# NIRGM_V9.net
KiCad netlist of a schematic drawn in EAGLE
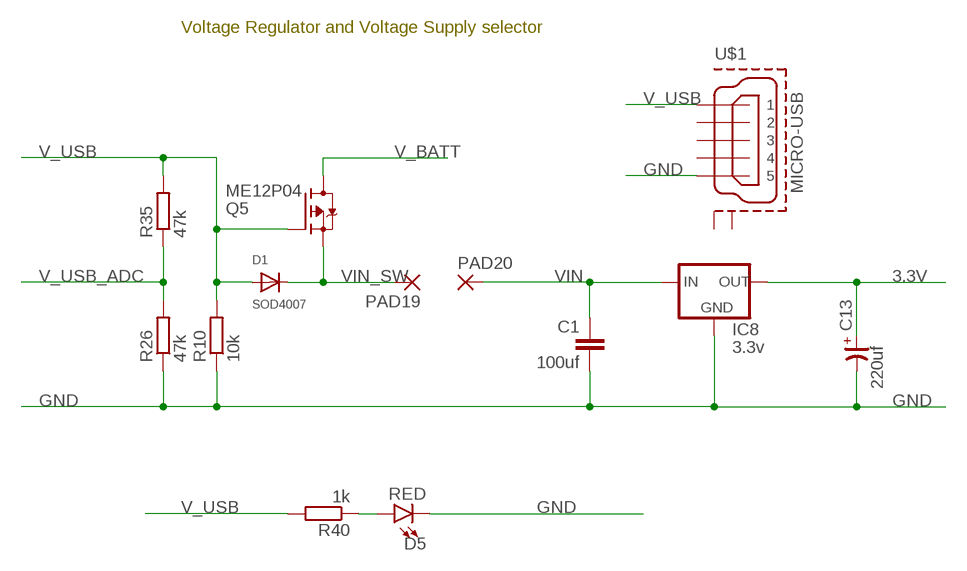
[diagram p0: schematic, sheet 1]
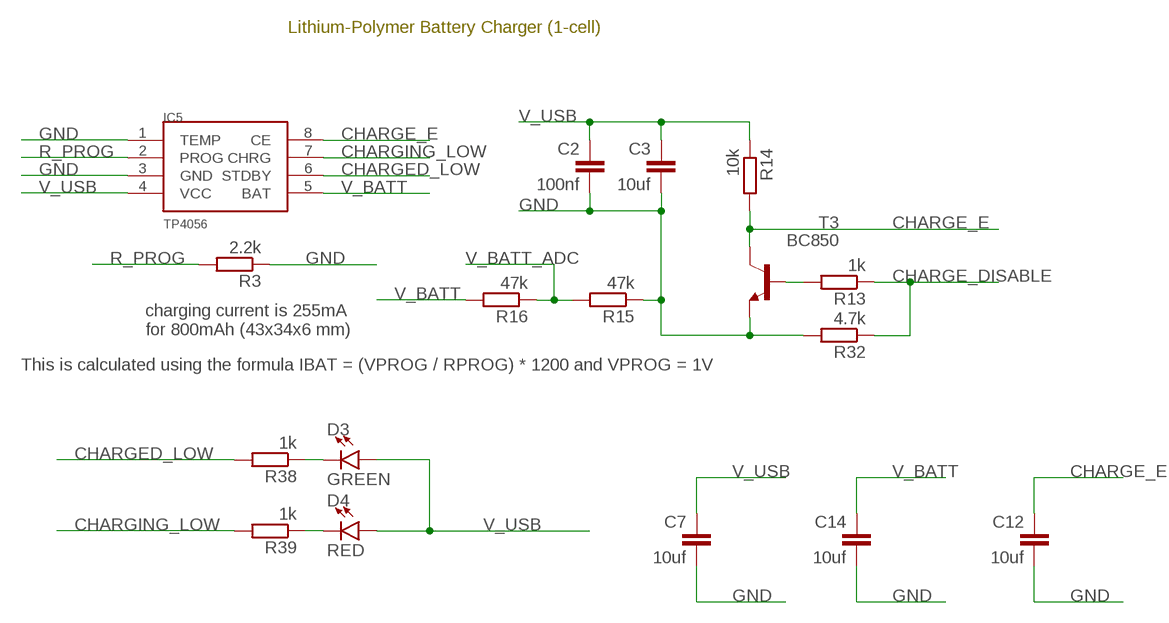
[diagram p1: schematic, sheet 2]
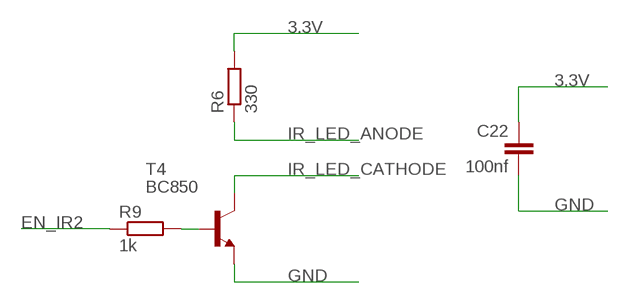
[diagram p2: schematic, sheet 3]
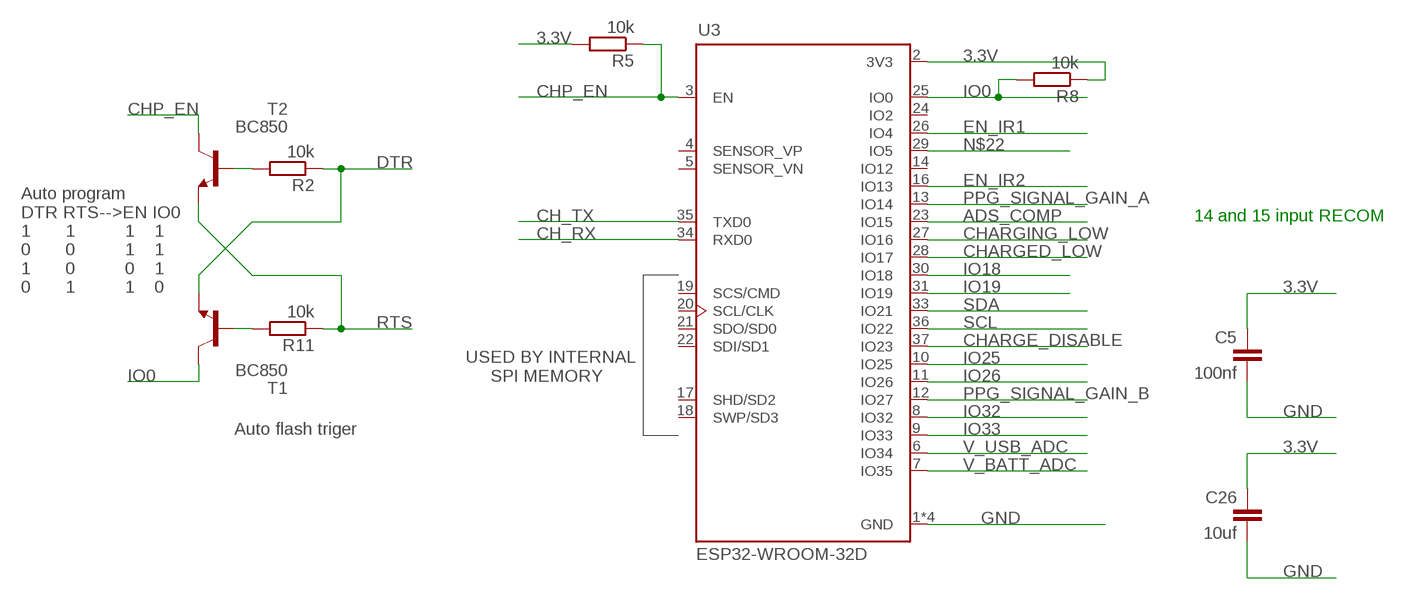
[diagram p3: schematic, sheet 4]
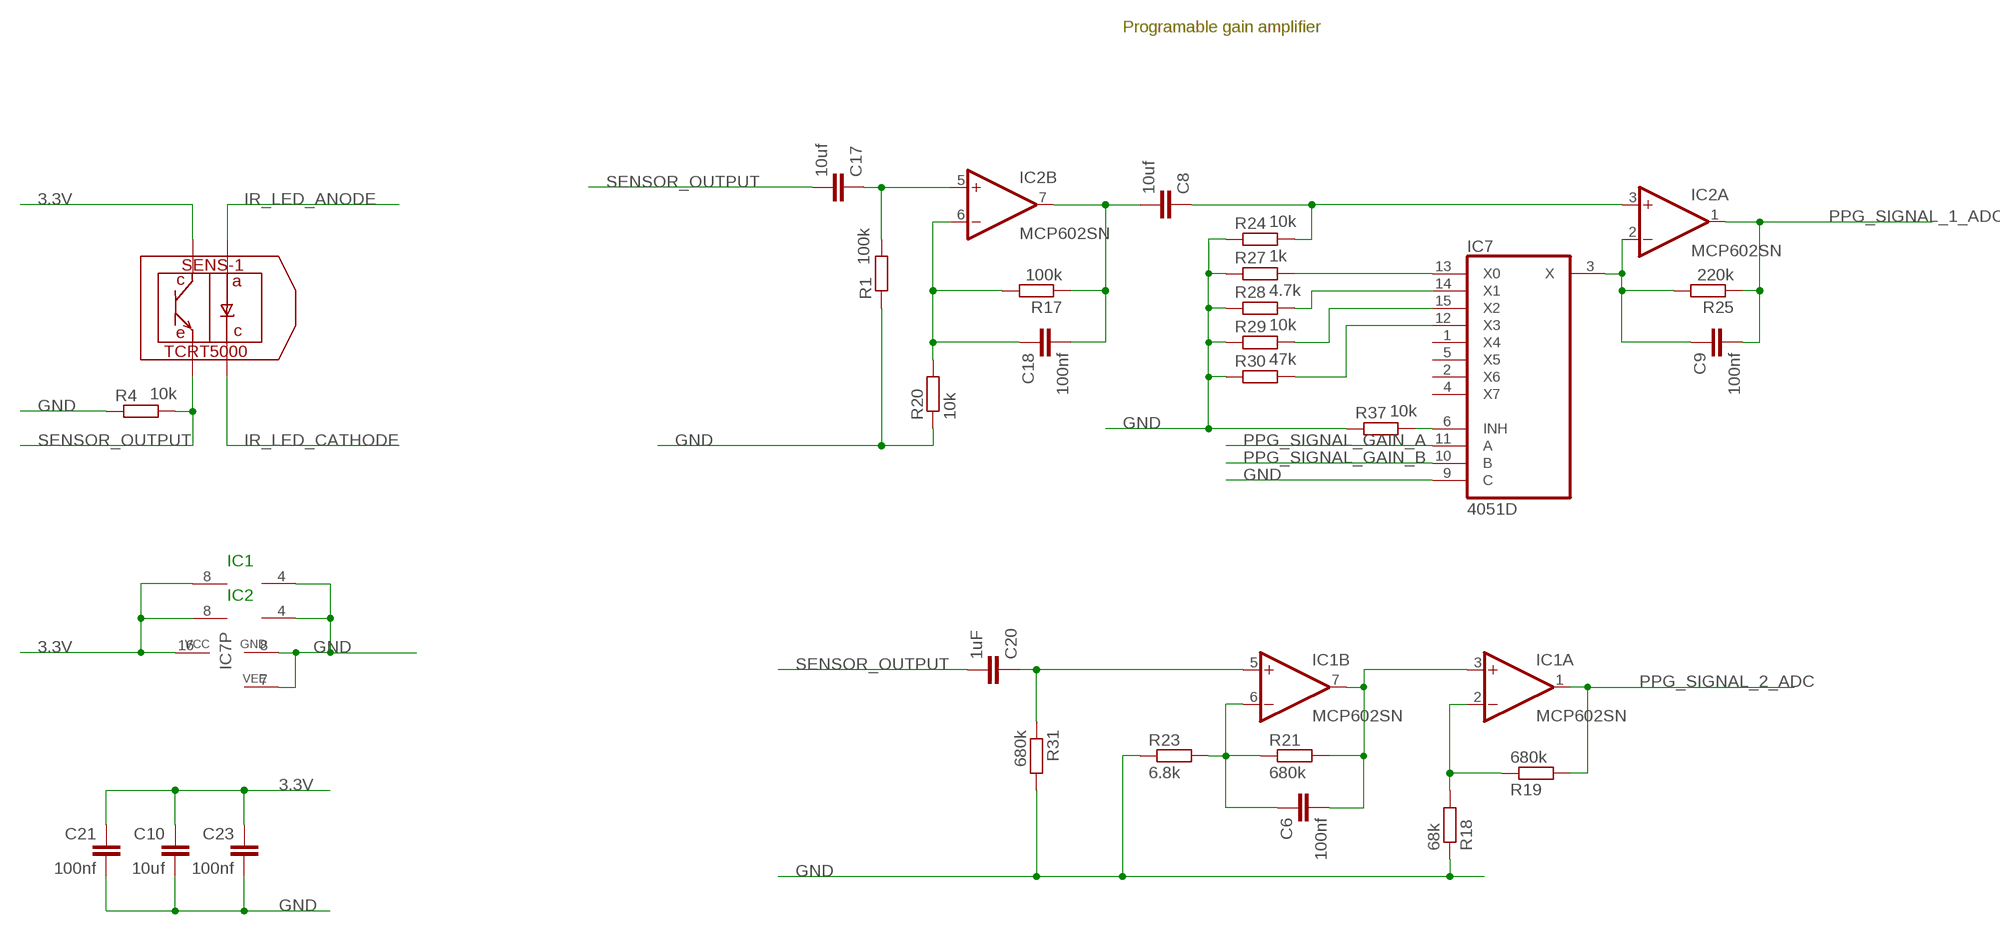
[diagram p4: schematic, sheet 5]
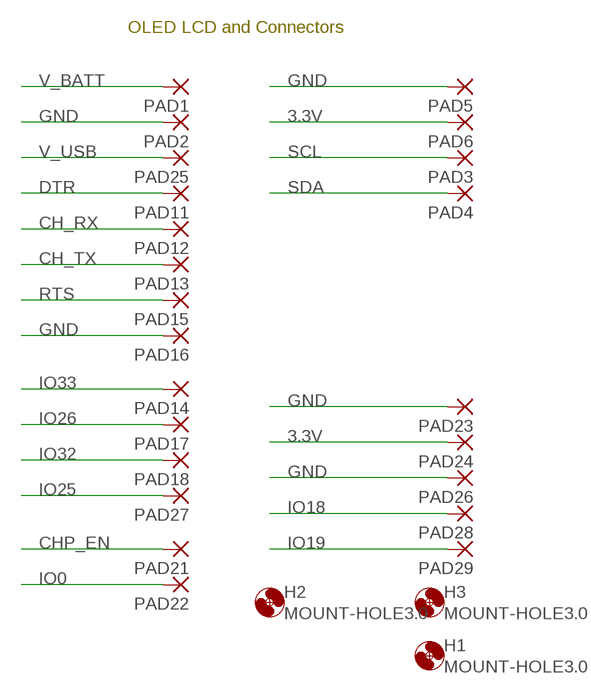
[diagram p5: schematic, sheet 6]
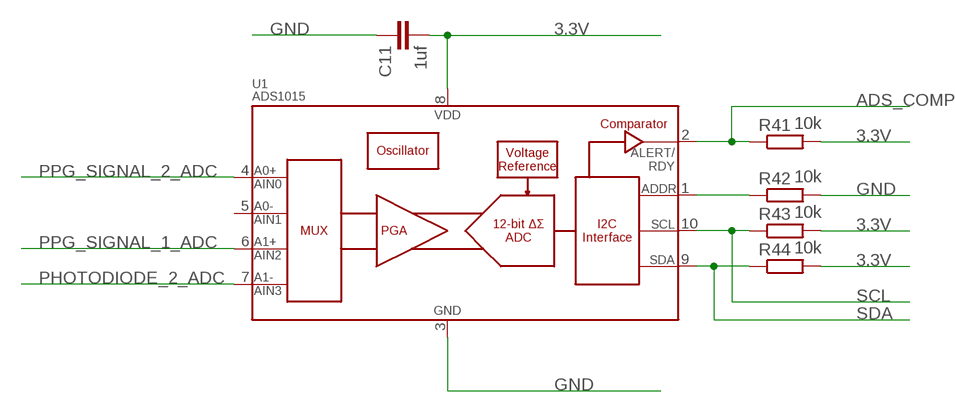
[diagram p6: schematic, sheet 7]

(export (version "E")
  (design (tool "Eeschema 10.0.6"))
  (components
    (comp (ref "H1")
      (value "MOUNT-HOLE3.0")
      (footprint "eagle-import:3,0")
      (libsource (lib "eagle-import") (part "MOUNT-HOLE3.0"))
    )
    (comp (ref "H2")
      (value "MOUNT-HOLE3.0")
      (footprint "eagle-import:3,0")
      (libsource (lib "eagle-import") (part "MOUNT-HOLE3.0"))
    )
    (comp (ref "H3")
      (value "MOUNT-HOLE3.0")
      (footprint "eagle-import:3,0")
      (libsource (lib "eagle-import") (part "MOUNT-HOLE3.0"))
    )
    (comp (ref "PAD1")
      (value "WIREPADSMD5-2,5")
      (footprint "eagle-import:5-2,5")
      (libsource (lib "eagle-import") (part "WIREPADSMD5-2,5"))
    )
    (comp (ref "PAD2")
      (value "WIREPADSMD5-2,5")
      (footprint "eagle-import:5-2,5")
      (libsource (lib "eagle-import") (part "WIREPADSMD5-2,5"))
    )
    (comp (ref "PAD3")
      (value "SMD2")
      (footprint "eagle-import:SMD1,27-2,54")
      (libsource (lib "eagle-import") (part "SMD2"))
    )
    (comp (ref "PAD4")
      (value "SMD2")
      (footprint "eagle-import:SMD1,27-2,54")
      (libsource (lib "eagle-import") (part "SMD2"))
    )
    (comp (ref "PAD5")
      (value "SMD2")
      (footprint "eagle-import:SMD1,27-2,54")
      (libsource (lib "eagle-import") (part "SMD2"))
    )
    (comp (ref "PAD6")
      (value "SMD2")
      (footprint "eagle-import:SMD1,27-2,54")
      (libsource (lib "eagle-import") (part "SMD2"))
    )
    (comp (ref "PAD11")
      (value "SMD2")
      (footprint "eagle-import:SMD1,27-2,54")
      (libsource (lib "eagle-import") (part "SMD2"))
    )
    (comp (ref "PAD12")
      (value "SMD2")
      (footprint "eagle-import:SMD1,27-2,54")
      (libsource (lib "eagle-import") (part "SMD2"))
    )
    (comp (ref "PAD13")
      (value "SMD2")
      (footprint "eagle-import:SMD1,27-2,54")
      (libsource (lib "eagle-import") (part "SMD2"))
    )
    (comp (ref "PAD14")
      (value "SMD2")
      (footprint "eagle-import:SMD1,27-2,54")
      (libsource (lib "eagle-import") (part "SMD2"))
    )
    (comp (ref "PAD15")
      (value "SMD2")
      (footprint "eagle-import:SMD1,27-2,54")
      (libsource (lib "eagle-import") (part "SMD2"))
    )
    (comp (ref "PAD16")
      (value "SMD2")
      (footprint "eagle-import:SMD1,27-2,54")
      (libsource (lib "eagle-import") (part "SMD2"))
    )
    (comp (ref "PAD17")
      (value "SMD2")
      (footprint "eagle-import:SMD1,27-2,54")
      (libsource (lib "eagle-import") (part "SMD2"))
    )
    (comp (ref "PAD18")
      (value "SMD2")
      (footprint "eagle-import:SMD1,27-2,54")
      (libsource (lib "eagle-import") (part "SMD2"))
    )
    (comp (ref "PAD21")
      (value "SMD2")
      (footprint "eagle-import:SMD1,27-2,54")
      (libsource (lib "eagle-import") (part "SMD2"))
    )
    (comp (ref "PAD22")
      (value "SMD2")
      (footprint "eagle-import:SMD1,27-2,54")
      (libsource (lib "eagle-import") (part "SMD2"))
    )
    (comp (ref "PAD23")
      (value "SMD2")
      (footprint "eagle-import:SMD1,27-2,54")
      (libsource (lib "eagle-import") (part "SMD2"))
    )
    (comp (ref "PAD24")
      (value "SMD2")
      (footprint "eagle-import:SMD1,27-2,54")
      (libsource (lib "eagle-import") (part "SMD2"))
    )
    (comp (ref "PAD25")
      (value "SMD2")
      (footprint "eagle-import:SMD1,27-2,54")
      (libsource (lib "eagle-import") (part "SMD2"))
    )
    (comp (ref "PAD26")
      (value "SMD2")
      (footprint "eagle-import:SMD1,27-2,54")
      (libsource (lib "eagle-import") (part "SMD2"))
    )
    (comp (ref "PAD27")
      (value "SMD2")
      (footprint "eagle-import:SMD1,27-2,54")
      (libsource (lib "eagle-import") (part "SMD2"))
    )
    (comp (ref "PAD28")
      (value "SMD2")
      (footprint "eagle-import:SMD1,27-2,54")
      (libsource (lib "eagle-import") (part "SMD2"))
    )
    (comp (ref "PAD29")
      (value "SMD2")
      (footprint "eagle-import:SMD1,27-2,54")
      (libsource (lib "eagle-import") (part "SMD2"))
    )
    (comp (ref "C6")
      (value "100nf")
      (footprint "eagle-import:C1206K")
      (libsource (lib "eagle-import") (part "C-EUC1206K"))
    )
    (comp (ref "C8")
      (value "10uf")
      (footprint "eagle-import:C1206K")
      (libsource (lib "eagle-import") (part "C-EUC1206K"))
    )
    (comp (ref "C9")
      (value "100nf")
      (footprint "eagle-import:C1206K")
      (libsource (lib "eagle-import") (part "C-EUC1206K"))
    )
    (comp (ref "C10")
      (value "10uf")
      (footprint "eagle-import:C1206K")
      (libsource (lib "eagle-import") (part "C-EUC1206K"))
    )
    (comp (ref "C17")
      (value "10uf")
      (footprint "eagle-import:C1206K")
      (libsource (lib "eagle-import") (part "C-EUC1206K"))
    )
    (comp (ref "C18")
      (value "100nf")
      (footprint "eagle-import:C1206K")
      (libsource (lib "eagle-import") (part "C-EUC1206K"))
    )
    (comp (ref "C20")
      (value "1uF")
      (footprint "eagle-import:C1206K")
      (libsource (lib "eagle-import") (part "C-EUC1206K"))
    )
    (comp (ref "C21")
      (value "100nf")
      (footprint "eagle-import:C1206K")
      (libsource (lib "eagle-import") (part "C-EUC1206K"))
    )
    (comp (ref "C23")
      (value "100nf")
      (footprint "eagle-import:C1206K")
      (libsource (lib "eagle-import") (part "C-EUC1206K"))
    )
    (comp (ref "IC1")
      (value "MCP602SN")
      (footprint "eagle-import:SO08")
      (libsource (lib "eagle-import") (part "linear_262_MCP602SN"))
    )
    (comp (ref "IC2")
      (value "MCP602SN")
      (footprint "eagle-import:SO08")
      (libsource (lib "eagle-import") (part "MCP602SN"))
    )
    (comp (ref "IC7")
      (value "4051D")
      (footprint "eagle-import:SO16")
      (libsource (lib "eagle-import") (part "4051D"))
    )
    (comp (ref "R1")
      (value "100k")
      (footprint "eagle-import:R1206")
      (libsource (lib "eagle-import") (part "R-EU_R1206"))
    )
    (comp (ref "R4")
      (value "10k")
      (footprint "eagle-import:R1206")
      (libsource (lib "eagle-import") (part "R-EU_R1206"))
    )
    (comp (ref "R17")
      (value "100k")
      (footprint "eagle-import:R1206")
      (libsource (lib "eagle-import") (part "R-EU_R1206"))
    )
    (comp (ref "R18")
      (value "68k")
      (footprint "eagle-import:R1206")
      (libsource (lib "eagle-import") (part "R-EU_R1206"))
    )
    (comp (ref "R19")
      (value "680k")
      (footprint "eagle-import:R1206")
      (libsource (lib "eagle-import") (part "R-EU_R1206"))
    )
    (comp (ref "R20")
      (value "10k")
      (footprint "eagle-import:R1206")
      (libsource (lib "eagle-import") (part "R-EU_R1206"))
    )
    (comp (ref "R21")
      (value "680k")
      (footprint "eagle-import:R1206")
      (libsource (lib "eagle-import") (part "R-EU_R1206"))
    )
    (comp (ref "R23")
      (value "6.8k")
      (footprint "eagle-import:R1206")
      (libsource (lib "eagle-import") (part "R-EU_R1206"))
    )
    (comp (ref "R24")
      (value "10k")
      (footprint "eagle-import:R1206")
      (libsource (lib "eagle-import") (part "R-EU_R1206"))
    )
    (comp (ref "R25")
      (value "220k")
      (footprint "eagle-import:R1206")
      (libsource (lib "eagle-import") (part "R-EU_R1206"))
    )
    (comp (ref "R27")
      (value "1k")
      (footprint "eagle-import:R1206")
      (libsource (lib "eagle-import") (part "R-EU_R1206"))
    )
    (comp (ref "R28")
      (value "4.7k")
      (footprint "eagle-import:R1206")
      (libsource (lib "eagle-import") (part "R-EU_R1206"))
    )
    (comp (ref "R29")
      (value "10k")
      (footprint "eagle-import:R1206")
      (libsource (lib "eagle-import") (part "R-EU_R1206"))
    )
    (comp (ref "R30")
      (value "47k")
      (footprint "eagle-import:R1206")
      (libsource (lib "eagle-import") (part "R-EU_R1206"))
    )
    (comp (ref "R31")
      (value "680k")
      (footprint "eagle-import:R1206")
      (libsource (lib "eagle-import") (part "R-EU_R1206"))
    )
    (comp (ref "R37")
      (value "10k")
      (footprint "eagle-import:R1206")
      (libsource (lib "eagle-import") (part "R-EU_R1206"))
    )
    (comp (ref "SENS-1")
      (value "TCRT5000")
      (footprint "eagle-import:5000")
      (libsource (lib "eagle-import") (part "TCRT5000"))
    )
    (comp (ref "C11")
      (value "1uf")
      (footprint "eagle-import:C1206K")
      (libsource (lib "eagle-import") (part "C-EUC1206K"))
    )
    (comp (ref "R41")
      (value "10k")
      (footprint "eagle-import:R1206")
      (libsource (lib "eagle-import") (part "R-EU_R1206"))
    )
    (comp (ref "R42")
      (value "10k")
      (footprint "eagle-import:R1206")
      (libsource (lib "eagle-import") (part "R-EU_R1206"))
    )
    (comp (ref "R43")
      (value "10k")
      (footprint "eagle-import:R1206")
      (libsource (lib "eagle-import") (part "R-EU_R1206"))
    )
    (comp (ref "R44")
      (value "10k")
      (footprint "eagle-import:R1206")
      (libsource (lib "eagle-import") (part "R-EU_R1206"))
    )
    (comp (ref "U1")
      (value "ADS1015")
      (footprint "eagle-import:MSOP10")
      (libsource (lib "eagle-import") (part "ADS1015"))
    )
    (comp (ref "C2")
      (value "100nf")
      (footprint "eagle-import:C1206K")
      (libsource (lib "eagle-import") (part "C-EUC1206K"))
    )
    (comp (ref "C3")
      (value "10uf")
      (footprint "eagle-import:C1206K")
      (libsource (lib "eagle-import") (part "C-EUC1206K"))
    )
    (comp (ref "C7")
      (value "10uf")
      (footprint "eagle-import:C1206K")
      (libsource (lib "eagle-import") (part "C-EUC1206K"))
    )
    (comp (ref "C12")
      (value "10uf")
      (footprint "eagle-import:C1206K")
      (libsource (lib "eagle-import") (part "C-EUC1206K"))
    )
    (comp (ref "C14")
      (value "10uf")
      (footprint "eagle-import:C1206K")
      (libsource (lib "eagle-import") (part "C-EUC1206K"))
    )
    (comp (ref "D3")
      (value "GREEN")
      (footprint "eagle-import:LED-1206")
      (libsource (lib "eagle-import") (part "LED-GREEN1206"))
    )
    (comp (ref "D4")
      (value "RED")
      (footprint "eagle-import:LED-1206")
      (libsource (lib "eagle-import") (part "LED-GREEN1206"))
    )
    (comp (ref "IC5")
      (value "TP4056")
      (footprint "eagle-import:SOP-8")
      (libsource (lib "eagle-import") (part "TP4056"))
    )
    (comp (ref "R3")
      (value "2.2k")
      (footprint "eagle-import:R1206")
      (libsource (lib "eagle-import") (part "R-EU_R1206"))
    )
    (comp (ref "R13")
      (value "1k")
      (footprint "eagle-import:R1206")
      (libsource (lib "eagle-import") (part "R-EU_R1206"))
    )
    (comp (ref "R14")
      (value "10k")
      (footprint "eagle-import:R1206")
      (libsource (lib "eagle-import") (part "R-EU_R1206"))
    )
    (comp (ref "R15")
      (value "47k")
      (footprint "eagle-import:R1206")
      (libsource (lib "eagle-import") (part "R-EU_R1206"))
    )
    (comp (ref "R16")
      (value "47k")
      (footprint "eagle-import:R1206")
      (libsource (lib "eagle-import") (part "R-EU_R1206"))
    )
    (comp (ref "R32")
      (value "4.7k")
      (footprint "eagle-import:R1206")
      (libsource (lib "eagle-import") (part "R-EU_R1206"))
    )
    (comp (ref "R38")
      (value "1k")
      (footprint "eagle-import:R1206")
      (libsource (lib "eagle-import") (part "R-EU_R1206"))
    )
    (comp (ref "R39")
      (value "1k")
      (footprint "eagle-import:R1206")
      (libsource (lib "eagle-import") (part "R-EU_R1206"))
    )
    (comp (ref "T3")
      (value "BC850")
      (footprint "eagle-import:SOT23")
      (libsource (lib "eagle-import") (part "BC850"))
    )
    (comp (ref "C1")
      (value "100uf")
      (footprint "eagle-import:C1206K")
      (libsource (lib "eagle-import") (part "C-EUC1206K"))
    )
    (comp (ref "C13")
      (value "220uf")
      (footprint "eagle-import:7343_T")
      (libsource (lib "eagle-import") (part "CP-7343"))
    )
    (comp (ref "D1")
      (value "SOD4007")
      (footprint "eagle-import:SOD-123FL")
      (libsource (lib "eagle-import") (part "DIODE_SOD-123FL"))
    )
    (comp (ref "D5")
      (value "RED")
      (footprint "eagle-import:LED-1206")
      (libsource (lib "eagle-import") (part "LED-GREEN1206"))
    )
    (comp (ref "IC8")
      (value "3.3v")
      (footprint "eagle-import:TO252")
      (libsource (lib "eagle-import") (part "LM1117TO252"))
    )
    (comp (ref "PAD19")
      (value "SMD2")
      (footprint "eagle-import:SMD1,27-2,54")
      (libsource (lib "eagle-import") (part "SMD2"))
    )
    (comp (ref "PAD20")
      (value "SMD2")
      (footprint "eagle-import:SMD1,27-2,54")
      (libsource (lib "eagle-import") (part "SMD2"))
    )
    (comp (ref "Q5")
      (value "ME12P04")
      (footprint "eagle-import:TO252")
      (libsource (lib "eagle-import") (part "FDD4141TO252"))
    )
    (comp (ref "R10")
      (value "10k")
      (footprint "eagle-import:R1206")
      (libsource (lib "eagle-import") (part "R-EU_R1206"))
    )
    (comp (ref "R26")
      (value "47k")
      (footprint "eagle-import:R1206")
      (libsource (lib "eagle-import") (part "R-EU_R1206"))
    )
    (comp (ref "R35")
      (value "47k")
      (footprint "eagle-import:R1206")
      (libsource (lib "eagle-import") (part "R-EU_R1206"))
    )
    (comp (ref "R40")
      (value "1k")
      (footprint "eagle-import:R1206")
      (libsource (lib "eagle-import") (part "R-EU_R1206"))
    )
    (comp (ref "U$1")
      (value "MICRO-USB")
      (footprint "eagle-import:47589-0001")
      (libsource (lib "eagle-import") (part "MICRO-USB-RECEPTACLE47589-0001"))
    )
    (comp (ref "C5")
      (value "100nf")
      (footprint "eagle-import:C1206K")
      (libsource (lib "eagle-import") (part "C-EUC1206K"))
    )
    (comp (ref "C26")
      (value "10uf")
      (footprint "eagle-import:C1206K")
      (libsource (lib "eagle-import") (part "C-EUC1206K"))
    )
    (comp (ref "R2")
      (value "10k")
      (footprint "eagle-import:R1206")
      (libsource (lib "eagle-import") (part "R-EU_R1206"))
    )
    (comp (ref "R5")
      (value "10k")
      (footprint "eagle-import:R1206")
      (libsource (lib "eagle-import") (part "R-EU_R1206"))
    )
    (comp (ref "R8")
      (value "10k")
      (footprint "eagle-import:R1206")
      (libsource (lib "eagle-import") (part "R-EU_R1206"))
    )
    (comp (ref "R11")
      (value "10k")
      (footprint "eagle-import:R1206")
      (libsource (lib "eagle-import") (part "R-EU_R1206"))
    )
    (comp (ref "T1")
      (value "BC850")
      (footprint "eagle-import:SOT23")
      (libsource (lib "eagle-import") (part "BC850"))
    )
    (comp (ref "T2")
      (value "BC850")
      (footprint "eagle-import:SOT23")
      (libsource (lib "eagle-import") (part "BC850"))
    )
    (comp (ref "U3")
      (value "ESP32-WROOM-32D")
      (footprint "eagle-import:MODULE_ESP32-WROOM-32D")
      (fields (field (name "MF") "Espressif Systems"))
      (libsource (lib "eagle-import") (part "ESP32-WROOM-32D"))
    )
    (comp (ref "C22")
      (value "100nf")
      (footprint "eagle-import:C1206K")
      (libsource (lib "eagle-import") (part "C-EUC1206K"))
    )
    (comp (ref "R6")
      (value "330")
      (footprint "eagle-import:R1206")
      (libsource (lib "eagle-import") (part "R-EU_R1206"))
    )
    (comp (ref "R9")
      (value "1k")
      (footprint "eagle-import:R1206")
      (libsource (lib "eagle-import") (part "R-EU_R1206"))
    )
    (comp (ref "T4")
      (value "BC850")
      (footprint "eagle-import:SOT23")
      (libsource (lib "eagle-import") (part "BC850"))
    )
  )
  (nets
    (net (code "1") (name "3.3V") (class "Default")
      (node (ref "C10") (pin "1") (pinfunction "1_1") (pintype "passive"))
      (node (ref "C11") (pin "2") (pinfunction "2_2") (pintype "passive"))
      (node (ref "C13") (pin "+") (pinfunction "+_+") (pintype "passive"))
      (node (ref "C21") (pin "1") (pinfunction "1_1") (pintype "passive"))
      (node (ref "C22") (pin "1") (pinfunction "1_1") (pintype "passive"))
      (node (ref "C23") (pin "1") (pinfunction "1_1") (pintype "passive"))
      (node (ref "C26") (pin "1") (pinfunction "1_1") (pintype "passive"))
      (node (ref "C5") (pin "1") (pinfunction "1_1") (pintype "passive"))
      (node (ref "IC1") (pin "8") (pinfunction "V+_8") (pintype "power_in"))
      (node (ref "IC2") (pin "8") (pinfunction "V+_8") (pintype "power_in"))
      (node (ref "IC7") (pin "16") (pinfunction "VCC_16") (pintype "power_in"))
      (node (ref "IC8") (pin "3") (pinfunction "OUT_3") (pintype "passive"))
      (node (ref "PAD24") (pin "1") (pinfunction "P_1") (pintype "passive"))
      (node (ref "PAD6") (pin "1") (pinfunction "P_1") (pintype "passive"))
      (node (ref "R41") (pin "2") (pinfunction "2_2") (pintype "passive"))
      (node (ref "R43") (pin "2") (pinfunction "2_2") (pintype "passive"))
      (node (ref "R44") (pin "2") (pinfunction "2_2") (pintype "passive"))
      (node (ref "R5") (pin "2") (pinfunction "2_2") (pintype "passive"))
      (node (ref "R6") (pin "2") (pinfunction "2_2") (pintype "passive"))
      (node (ref "R8") (pin "1") (pinfunction "1_1") (pintype "passive"))
      (node (ref "SENS-1") (pin "P$1") (pinfunction "P$1_P$1") (pintype "passive"))
      (node (ref "U1") (pin "8") (pinfunction "VDD_8") (pintype "bidirectional"))
      (node (ref "U3") (pin "2") (pinfunction "3V3_2") (pintype "power_in"))
    )
    (net (code "2") (name "ADS_COMP") (class "Default")
      (node (ref "R41") (pin "1") (pinfunction "1_1") (pintype "passive"))
      (node (ref "U1") (pin "2") (pinfunction "ALERT/RDY_2") (pintype "bidirectional"))
      (node (ref "U3") (pin "23") (pinfunction "IO15_23") (pintype "bidirectional"))
    )
    (net (code "3") (name "CHARGED_LOW") (class "Default")
      (node (ref "IC5") (pin "6") (pinfunction "STDBY_6") (pintype "bidirectional"))
      (node (ref "R38") (pin "2") (pinfunction "2_2") (pintype "passive"))
      (node (ref "U3") (pin "28") (pinfunction "IO17_28") (pintype "bidirectional"))
    )
    (net (code "4") (name "CHARGE_DISABLE") (class "Default")
      (node (ref "R13") (pin "1") (pinfunction "1_1") (pintype "passive"))
      (node (ref "R32") (pin "1") (pinfunction "1_1") (pintype "passive"))
      (node (ref "U3") (pin "37") (pinfunction "IO23_37") (pintype "bidirectional"))
    )
    (net (code "5") (name "CHARGE_E") (class "Default")
      (node (ref "C12") (pin "1") (pinfunction "1_1") (pintype "passive"))
      (node (ref "IC5") (pin "8") (pinfunction "CE_8") (pintype "bidirectional"))
      (node (ref "R14") (pin "2") (pinfunction "2_2") (pintype "passive"))
      (node (ref "T3") (pin "3") (pinfunction "C_3") (pintype "passive"))
    )
    (net (code "6") (name "CHARGING_LOW") (class "Default")
      (node (ref "IC5") (pin "7") (pinfunction "CHRG_7") (pintype "bidirectional"))
      (node (ref "R39") (pin "2") (pinfunction "2_2") (pintype "passive"))
      (node (ref "U3") (pin "27") (pinfunction "IO16_27") (pintype "bidirectional"))
    )
    (net (code "7") (name "CHP_EN") (class "Default")
      (node (ref "PAD21") (pin "1") (pinfunction "P_1") (pintype "passive"))
      (node (ref "R5") (pin "1") (pinfunction "1_1") (pintype "passive"))
      (node (ref "T2") (pin "3") (pinfunction "C_3") (pintype "passive"))
      (node (ref "U3") (pin "3") (pinfunction "EN_3") (pintype "input"))
    )
    (net (code "8") (name "CH_RX") (class "Default")
      (node (ref "PAD12") (pin "1") (pinfunction "P_1") (pintype "passive"))
      (node (ref "U3") (pin "34") (pinfunction "RXD0_34") (pintype "bidirectional"))
    )
    (net (code "9") (name "CH_TX") (class "Default")
      (node (ref "PAD13") (pin "1") (pinfunction "P_1") (pintype "passive"))
      (node (ref "U3") (pin "35") (pinfunction "TXD0_35") (pintype "bidirectional"))
    )
    (net (code "10") (name "DTR") (class "Default")
      (node (ref "PAD11") (pin "1") (pinfunction "P_1") (pintype "passive"))
      (node (ref "R2") (pin "1") (pinfunction "1_1") (pintype "passive"))
      (node (ref "T1") (pin "2") (pinfunction "E_2") (pintype "passive"))
    )
    (net (code "11") (name "EN_IR1") (class "Default")
      (node (ref "U3") (pin "26") (pinfunction "IO4_26") (pintype "bidirectional"))
    )
    (net (code "12") (name "EN_IR2") (class "Default")
      (node (ref "R9") (pin "1") (pinfunction "1_1") (pintype "passive"))
      (node (ref "U3") (pin "16") (pinfunction "IO13_16") (pintype "bidirectional"))
    )
    (net (code "13") (name "GND") (class "Default")
      (node (ref "C1") (pin "2") (pinfunction "2_2") (pintype "passive"))
      (node (ref "C10") (pin "2") (pinfunction "2_2") (pintype "passive"))
      (node (ref "C11") (pin "1") (pinfunction "1_1") (pintype "passive"))
      (node (ref "C12") (pin "2") (pinfunction "2_2") (pintype "passive"))
      (node (ref "C13") (pin "-") (pinfunction "-_-") (pintype "passive"))
      (node (ref "C14") (pin "2") (pinfunction "2_2") (pintype "passive"))
      (node (ref "C2") (pin "2") (pinfunction "2_2") (pintype "passive"))
      (node (ref "C21") (pin "2") (pinfunction "2_2") (pintype "passive"))
      (node (ref "C22") (pin "2") (pinfunction "2_2") (pintype "passive"))
      (node (ref "C23") (pin "2") (pinfunction "2_2") (pintype "passive"))
      (node (ref "C26") (pin "2") (pinfunction "2_2") (pintype "passive"))
      (node (ref "C3") (pin "2") (pinfunction "2_2") (pintype "passive"))
      (node (ref "C5") (pin "2") (pinfunction "2_2") (pintype "passive"))
      (node (ref "C7") (pin "2") (pinfunction "2_2") (pintype "passive"))
      (node (ref "D5") (pin "C") (pinfunction "C_C") (pintype "passive"))
      (node (ref "IC1") (pin "4") (pinfunction "V-_4") (pintype "power_in"))
      (node (ref "IC2") (pin "4") (pinfunction "V-_4") (pintype "power_in"))
      (node (ref "IC5") (pin "1") (pinfunction "TEMP_1") (pintype "bidirectional"))
      (node (ref "IC5") (pin "3") (pinfunction "GND_3") (pintype "bidirectional"))
      (node (ref "IC7") (pin "7") (pinfunction "VEE_7") (pintype "power_in"))
      (node (ref "IC7") (pin "8") (pinfunction "GND_8") (pintype "power_in"))
      (node (ref "IC7") (pin "9") (pinfunction "C_9") (pintype "input"))
      (node (ref "IC8") (pin "1") (pinfunction "GND_1") (pintype "input"))
      (node (ref "PAD16") (pin "1") (pinfunction "P_1") (pintype "passive"))
      (node (ref "PAD2") (pin "1") (pinfunction "P_1") (pintype "passive"))
      (node (ref "PAD23") (pin "1") (pinfunction "P_1") (pintype "passive"))
      (node (ref "PAD26") (pin "1") (pinfunction "P_1") (pintype "passive"))
      (node (ref "PAD5") (pin "1") (pinfunction "P_1") (pintype "passive"))
      (node (ref "R1") (pin "1") (pinfunction "1_1") (pintype "passive"))
      (node (ref "R10") (pin "1") (pinfunction "1_1") (pintype "passive"))
      (node (ref "R15") (pin "1") (pinfunction "1_1") (pintype "passive"))
      (node (ref "R18") (pin "1") (pinfunction "1_1") (pintype "passive"))
      (node (ref "R20") (pin "1") (pinfunction "1_1") (pintype "passive"))
      (node (ref "R23") (pin "1") (pinfunction "1_1") (pintype "passive"))
      (node (ref "R24") (pin "1") (pinfunction "1_1") (pintype "passive"))
      (node (ref "R26") (pin "1") (pinfunction "1_1") (pintype "passive"))
      (node (ref "R27") (pin "1") (pinfunction "1_1") (pintype "passive"))
      (node (ref "R28") (pin "1") (pinfunction "1_1") (pintype "passive"))
      (node (ref "R29") (pin "1") (pinfunction "1_1") (pintype "passive"))
      (node (ref "R3") (pin "1") (pinfunction "1_1") (pintype "passive"))
      (node (ref "R30") (pin "1") (pinfunction "1_1") (pintype "passive"))
      (node (ref "R31") (pin "2") (pinfunction "2_2") (pintype "passive"))
      (node (ref "R32") (pin "2") (pinfunction "2_2") (pintype "passive"))
      (node (ref "R37") (pin "1") (pinfunction "1_1") (pintype "passive"))
      (node (ref "R4") (pin "1") (pinfunction "1_1") (pintype "passive"))
      (node (ref "R42") (pin "2") (pinfunction "2_2") (pintype "passive"))
      (node (ref "T3") (pin "2") (pinfunction "E_2") (pintype "passive"))
      (node (ref "T4") (pin "2") (pinfunction "E_2") (pintype "passive"))
      (node (ref "U$1") (pin "5") (pinfunction "5_5") (pintype "input"))
      (node (ref "U1") (pin "3") (pinfunction "VSS_3") (pintype "bidirectional"))
      (node (ref "U3") (pin "1") (pinfunction "GND_1") (pintype "power_in"))
      (node (ref "U3") (pin "15") (pinfunction "GND_15") (pintype "power_in"))
      (node (ref "U3") (pin "38") (pinfunction "GND_38") (pintype "power_in"))
      (node (ref "U3") (pin "39") (pinfunction "GND_39") (pintype "power_in"))
    )
    (net (code "14") (name "IO0") (class "Default")
      (node (ref "PAD22") (pin "1") (pinfunction "P_1") (pintype "passive"))
      (node (ref "R8") (pin "2") (pinfunction "2_2") (pintype "passive"))
      (node (ref "T1") (pin "3") (pinfunction "C_3") (pintype "passive"))
      (node (ref "U3") (pin "25") (pinfunction "IO0_25") (pintype "bidirectional"))
    )
    (net (code "15") (name "IO18") (class "Default")
      (node (ref "PAD28") (pin "1") (pinfunction "P_1") (pintype "passive"))
      (node (ref "U3") (pin "30") (pinfunction "IO18_30") (pintype "bidirectional"))
    )
    (net (code "16") (name "IO19") (class "Default")
      (node (ref "PAD29") (pin "1") (pinfunction "P_1") (pintype "passive"))
      (node (ref "U3") (pin "31") (pinfunction "IO19_31") (pintype "bidirectional"))
    )
    (net (code "17") (name "IO25") (class "Default")
      (node (ref "PAD27") (pin "1") (pinfunction "P_1") (pintype "passive"))
      (node (ref "U3") (pin "10") (pinfunction "IO25_10") (pintype "bidirectional"))
    )
    (net (code "18") (name "IO26") (class "Default")
      (node (ref "PAD17") (pin "1") (pinfunction "P_1") (pintype "passive"))
      (node (ref "U3") (pin "11") (pinfunction "IO26_11") (pintype "bidirectional"))
    )
    (net (code "19") (name "IO32") (class "Default")
      (node (ref "PAD18") (pin "1") (pinfunction "P_1") (pintype "passive"))
      (node (ref "U3") (pin "8") (pinfunction "IO32_8") (pintype "bidirectional"))
    )
    (net (code "20") (name "IO33") (class "Default")
      (node (ref "PAD14") (pin "1") (pinfunction "P_1") (pintype "passive"))
      (node (ref "U3") (pin "9") (pinfunction "IO33_9") (pintype "bidirectional"))
    )
    (net (code "21") (name "IR_LED_ANODE") (class "Default")
      (node (ref "R6") (pin "1") (pinfunction "1_1") (pintype "passive"))
      (node (ref "SENS-1") (pin "P$3") (pinfunction "P$3_P$3") (pintype "passive"))
    )
    (net (code "22") (name "IR_LED_CATHODE") (class "Default")
      (node (ref "SENS-1") (pin "P$4") (pinfunction "P$4_P$4") (pintype "passive"))
      (node (ref "T4") (pin "3") (pinfunction "C_3") (pintype "passive"))
    )
    (net (code "23") (name "N$22") (class "Default")
      (node (ref "U3") (pin "29") (pinfunction "IO5_29") (pintype "bidirectional"))
    )
    (net (code "24") (name "Net-(D3-PadC)") (class "Default")
      (node (ref "D3") (pin "C") (pinfunction "C_C") (pintype "passive"))
      (node (ref "R38") (pin "1") (pinfunction "1_1") (pintype "passive"))
    )
    (net (code "25") (name "Net-(D4-PadC)") (class "Default")
      (node (ref "D4") (pin "C") (pinfunction "C_C") (pintype "passive"))
      (node (ref "R39") (pin "1") (pinfunction "1_1") (pintype "passive"))
    )
    (net (code "26") (name "Net-(D5-PadA)") (class "Default")
      (node (ref "D5") (pin "A") (pinfunction "A_A") (pintype "passive"))
      (node (ref "R40") (pin "1") (pinfunction "1_1") (pintype "passive"))
    )
    (net (code "27") (name "Net-(IC1A-+IN)") (class "Default")
      (node (ref "C6") (pin "2") (pinfunction "2_2") (pintype "passive"))
      (node (ref "IC1") (pin "3") (pinfunction "+IN_3") (pintype "input"))
      (node (ref "IC1") (pin "7") (pinfunction "OUT_7") (pintype "output"))
      (node (ref "R21") (pin "2") (pinfunction "2_2") (pintype "passive"))
    )
    (net (code "28") (name "Net-(IC1A--IN)") (class "Default")
      (node (ref "IC1") (pin "2") (pinfunction "-IN_2") (pintype "input"))
      (node (ref "R18") (pin "2") (pinfunction "2_2") (pintype "passive"))
      (node (ref "R19") (pin "1") (pinfunction "1_1") (pintype "passive"))
    )
    (net (code "29") (name "Net-(IC1B-+IN)") (class "Default")
      (node (ref "C20") (pin "1") (pinfunction "1_1") (pintype "passive"))
      (node (ref "IC1") (pin "5") (pinfunction "+IN_5") (pintype "input"))
      (node (ref "R31") (pin "1") (pinfunction "1_1") (pintype "passive"))
    )
    (net (code "30") (name "Net-(IC1B--IN)") (class "Default")
      (node (ref "C6") (pin "1") (pinfunction "1_1") (pintype "passive"))
      (node (ref "IC1") (pin "6") (pinfunction "-IN_6") (pintype "input"))
      (node (ref "R21") (pin "1") (pinfunction "1_1") (pintype "passive"))
      (node (ref "R23") (pin "2") (pinfunction "2_2") (pintype "passive"))
    )
    (net (code "31") (name "Net-(IC2A-+IN)") (class "Default")
      (node (ref "C8") (pin "1") (pinfunction "1_1") (pintype "passive"))
      (node (ref "IC2") (pin "3") (pinfunction "+IN_3") (pintype "input"))
      (node (ref "R24") (pin "2") (pinfunction "2_2") (pintype "passive"))
    )
    (net (code "32") (name "Net-(IC2A--IN)") (class "Default")
      (node (ref "C9") (pin "1") (pinfunction "1_1") (pintype "passive"))
      (node (ref "IC2") (pin "2") (pinfunction "-IN_2") (pintype "input"))
      (node (ref "IC7") (pin "3") (pinfunction "X_3") (pintype "bidirectional"))
      (node (ref "R25") (pin "2") (pinfunction "2_2") (pintype "passive"))
    )
    (net (code "33") (name "Net-(IC2B-+IN)") (class "Default")
      (node (ref "C17") (pin "1") (pinfunction "1_1") (pintype "passive"))
      (node (ref "IC2") (pin "5") (pinfunction "+IN_5") (pintype "input"))
      (node (ref "R1") (pin "2") (pinfunction "2_2") (pintype "passive"))
    )
    (net (code "34") (name "Net-(IC2B--IN)") (class "Default")
      (node (ref "C18") (pin "1") (pinfunction "1_1") (pintype "passive"))
      (node (ref "IC2") (pin "6") (pinfunction "-IN_6") (pintype "input"))
      (node (ref "R17") (pin "2") (pinfunction "2_2") (pintype "passive"))
      (node (ref "R20") (pin "2") (pinfunction "2_2") (pintype "passive"))
    )
    (net (code "35") (name "Net-(IC2B-OUT)") (class "Default")
      (node (ref "C18") (pin "2") (pinfunction "2_2") (pintype "passive"))
      (node (ref "C8") (pin "2") (pinfunction "2_2") (pintype "passive"))
      (node (ref "IC2") (pin "7") (pinfunction "OUT_7") (pintype "output"))
      (node (ref "R17") (pin "1") (pinfunction "1_1") (pintype "passive"))
    )
    (net (code "36") (name "Net-(IC7A-INH)") (class "Default")
      (node (ref "IC7") (pin "6") (pinfunction "INH_6") (pintype "input"))
      (node (ref "R37") (pin "2") (pinfunction "2_2") (pintype "passive"))
    )
    (net (code "37") (name "Net-(IC7A-X0)") (class "Default")
      (node (ref "IC7") (pin "13") (pinfunction "X0_13") (pintype "bidirectional"))
      (node (ref "R27") (pin "2") (pinfunction "2_2") (pintype "passive"))
    )
    (net (code "38") (name "Net-(IC7A-X1)") (class "Default")
      (node (ref "IC7") (pin "14") (pinfunction "X1_14") (pintype "bidirectional"))
      (node (ref "R28") (pin "2") (pinfunction "2_2") (pintype "passive"))
    )
    (net (code "39") (name "Net-(IC7A-X2)") (class "Default")
      (node (ref "IC7") (pin "15") (pinfunction "X2_15") (pintype "bidirectional"))
      (node (ref "R29") (pin "2") (pinfunction "2_2") (pintype "passive"))
    )
    (net (code "40") (name "Net-(IC7A-X3)") (class "Default")
      (node (ref "IC7") (pin "12") (pinfunction "X3_12") (pintype "bidirectional"))
      (node (ref "R30") (pin "2") (pinfunction "2_2") (pintype "passive"))
    )
    (net (code "41") (name "Net-(T1-B)") (class "Default")
      (node (ref "R11") (pin "2") (pinfunction "2_2") (pintype "passive"))
      (node (ref "T1") (pin "1") (pinfunction "B_1") (pintype "passive"))
    )
    (net (code "42") (name "Net-(T2-B)") (class "Default")
      (node (ref "R2") (pin "2") (pinfunction "2_2") (pintype "passive"))
      (node (ref "T2") (pin "1") (pinfunction "B_1") (pintype "passive"))
    )
    (net (code "43") (name "Net-(T3-B)") (class "Default")
      (node (ref "R13") (pin "2") (pinfunction "2_2") (pintype "passive"))
      (node (ref "T3") (pin "1") (pinfunction "B_1") (pintype "passive"))
    )
    (net (code "44") (name "Net-(T4-B)") (class "Default")
      (node (ref "R9") (pin "2") (pinfunction "2_2") (pintype "passive"))
      (node (ref "T4") (pin "1") (pinfunction "B_1") (pintype "passive"))
    )
    (net (code "45") (name "Net-(U1-ADDR)") (class "Default")
      (node (ref "R42") (pin "1") (pinfunction "1_1") (pintype "passive"))
      (node (ref "U1") (pin "1") (pinfunction "ADDR_1") (pintype "bidirectional"))
    )
    (net (code "46") (name "PHOTODIODE_2_ADC") (class "Default")
      (node (ref "U1") (pin "7") (pinfunction "AIN3_7") (pintype "bidirectional"))
    )
    (net (code "47") (name "PPG_SIGNAL_1_ADC") (class "Default")
      (node (ref "C9") (pin "2") (pinfunction "2_2") (pintype "passive"))
      (node (ref "IC2") (pin "1") (pinfunction "OUT_1") (pintype "output"))
      (node (ref "R25") (pin "1") (pinfunction "1_1") (pintype "passive"))
      (node (ref "U1") (pin "6") (pinfunction "AIN2_6") (pintype "bidirectional"))
    )
    (net (code "48") (name "PPG_SIGNAL_2_ADC") (class "Default")
      (node (ref "IC1") (pin "1") (pinfunction "OUT_1") (pintype "output"))
      (node (ref "R19") (pin "2") (pinfunction "2_2") (pintype "passive"))
      (node (ref "U1") (pin "4") (pinfunction "AIN0_4") (pintype "bidirectional"))
    )
    (net (code "49") (name "PPG_SIGNAL_GAIN_A") (class "Default")
      (node (ref "IC7") (pin "11") (pinfunction "A_11") (pintype "input"))
      (node (ref "U3") (pin "13") (pinfunction "IO14_13") (pintype "bidirectional"))
    )
    (net (code "50") (name "PPG_SIGNAL_GAIN_B") (class "Default")
      (node (ref "IC7") (pin "10") (pinfunction "B_10") (pintype "input"))
      (node (ref "U3") (pin "12") (pinfunction "IO27_12") (pintype "bidirectional"))
    )
    (net (code "51") (name "RTS") (class "Default")
      (node (ref "PAD15") (pin "1") (pinfunction "P_1") (pintype "passive"))
      (node (ref "R11") (pin "1") (pinfunction "1_1") (pintype "passive"))
      (node (ref "T2") (pin "2") (pinfunction "E_2") (pintype "passive"))
    )
    (net (code "52") (name "R_PROG") (class "Default")
      (node (ref "IC5") (pin "2") (pinfunction "PROG_2") (pintype "bidirectional"))
      (node (ref "R3") (pin "2") (pinfunction "2_2") (pintype "passive"))
    )
    (net (code "53") (name "SCL") (class "Default")
      (node (ref "PAD3") (pin "1") (pinfunction "P_1") (pintype "passive"))
      (node (ref "R43") (pin "1") (pinfunction "1_1") (pintype "passive"))
      (node (ref "U1") (pin "10") (pinfunction "SCL_10") (pintype "bidirectional"))
      (node (ref "U3") (pin "36") (pinfunction "IO22_36") (pintype "bidirectional"))
    )
    (net (code "54") (name "SDA") (class "Default")
      (node (ref "PAD4") (pin "1") (pinfunction "P_1") (pintype "passive"))
      (node (ref "R44") (pin "1") (pinfunction "1_1") (pintype "passive"))
      (node (ref "U1") (pin "9") (pinfunction "SDA_9") (pintype "bidirectional"))
      (node (ref "U3") (pin "33") (pinfunction "IO21_33") (pintype "bidirectional"))
    )
    (net (code "55") (name "SENSOR_OUTPUT") (class "Default")
      (node (ref "C17") (pin "2") (pinfunction "2_2") (pintype "passive"))
      (node (ref "C20") (pin "2") (pinfunction "2_2") (pintype "passive"))
      (node (ref "R4") (pin "2") (pinfunction "2_2") (pintype "passive"))
      (node (ref "SENS-1") (pin "P$2") (pinfunction "P$2_P$2") (pintype "passive"))
    )
    (net (code "56") (name "VIN") (class "Default")
      (node (ref "C1") (pin "1") (pinfunction "1_1") (pintype "passive"))
      (node (ref "IC8") (pin "2") (pinfunction "IN_2") (pintype "input"))
      (node (ref "PAD20") (pin "1") (pinfunction "P_1") (pintype "passive"))
    )
    (net (code "57") (name "VIN_SW") (class "Default")
      (node (ref "D1") (pin "C") (pinfunction "C_C") (pintype "passive"))
      (node (ref "PAD19") (pin "1") (pinfunction "P_1") (pintype "passive"))
      (node (ref "Q5") (pin "2") (pinfunction "S_2") (pintype "passive"))
    )
    (net (code "58") (name "V_BATT") (class "Default")
      (node (ref "C14") (pin "1") (pinfunction "1_1") (pintype "passive"))
      (node (ref "IC5") (pin "5") (pinfunction "BAT_5") (pintype "bidirectional"))
      (node (ref "PAD1") (pin "1") (pinfunction "P_1") (pintype "passive"))
      (node (ref "Q5") (pin "3") (pinfunction "D_3") (pintype "passive"))
      (node (ref "R16") (pin "2") (pinfunction "2_2") (pintype "passive"))
    )
    (net (code "59") (name "V_BATT_ADC") (class "Default")
      (node (ref "R15") (pin "2") (pinfunction "2_2") (pintype "passive"))
      (node (ref "R16") (pin "1") (pinfunction "1_1") (pintype "passive"))
      (node (ref "U3") (pin "7") (pinfunction "IO35_7") (pintype "bidirectional"))
    )
    (net (code "60") (name "V_USB") (class "Default")
      (node (ref "C2") (pin "1") (pinfunction "1_1") (pintype "passive"))
      (node (ref "C3") (pin "1") (pinfunction "1_1") (pintype "passive"))
      (node (ref "C7") (pin "1") (pinfunction "1_1") (pintype "passive"))
      (node (ref "D1") (pin "A") (pinfunction "A_A") (pintype "passive"))
      (node (ref "D3") (pin "A") (pinfunction "A_A") (pintype "passive"))
      (node (ref "D4") (pin "A") (pinfunction "A_A") (pintype "passive"))
      (node (ref "IC5") (pin "4") (pinfunction "VCC_4") (pintype "bidirectional"))
      (node (ref "PAD25") (pin "1") (pinfunction "P_1") (pintype "passive"))
      (node (ref "Q5") (pin "1") (pinfunction "G_1") (pintype "passive"))
      (node (ref "R10") (pin "2") (pinfunction "2_2") (pintype "passive"))
      (node (ref "R14") (pin "1") (pinfunction "1_1") (pintype "passive"))
      (node (ref "R35") (pin "2") (pinfunction "2_2") (pintype "passive"))
      (node (ref "R40") (pin "2") (pinfunction "2_2") (pintype "passive"))
      (node (ref "U$1") (pin "1") (pinfunction "1_1") (pintype "input"))
    )
    (net (code "61") (name "V_USB_ADC") (class "Default")
      (node (ref "R26") (pin "2") (pinfunction "2_2") (pintype "passive"))
      (node (ref "R35") (pin "1") (pinfunction "1_1") (pintype "passive"))
      (node (ref "U3") (pin "6") (pinfunction "IO34_6") (pintype "bidirectional"))
    )
    (net (code "62") (name "unconnected-(IC7A-X4-Pad1)") (class "Default")
      (node (ref "IC7") (pin "1") (pinfunction "X4_1") (pintype "bidirectional"))
    )
    (net (code "63") (name "unconnected-(IC7A-X5-Pad5)") (class "Default")
      (node (ref "IC7") (pin "5") (pinfunction "X5_5") (pintype "bidirectional"))
    )
    (net (code "64") (name "unconnected-(IC7A-X6-Pad2)") (class "Default")
      (node (ref "IC7") (pin "2") (pinfunction "X6_2") (pintype "bidirectional"))
    )
    (net (code "65") (name "unconnected-(IC7A-X7-Pad4)") (class "Default")
      (node (ref "IC7") (pin "4") (pinfunction "X7_4") (pintype "bidirectional"))
    )
    (net (code "66") (name "unconnected-(U$1-GND1-PadP$1)") (class "Default")
      (node (ref "U$1") (pin "P$1") (pinfunction "GND1_P$1") (pintype "bidirectional"))
    )
    (net (code "67") (name "unconnected-(U$1-GND2-PadP$2)") (class "Default")
      (node (ref "U$1") (pin "P$2") (pinfunction "GND2_P$2") (pintype "bidirectional"))
    )
    (net (code "68") (name "unconnected-(U$1-Pad2)") (class "Default")
      (node (ref "U$1") (pin "2") (pinfunction "2_2") (pintype "input"))
    )
    (net (code "69") (name "unconnected-(U$1-Pad3)") (class "Default")
      (node (ref "U$1") (pin "3") (pinfunction "3_3") (pintype "input"))
    )
    (net (code "70") (name "unconnected-(U$1-Pad4)") (class "Default")
      (node (ref "U$1") (pin "4") (pinfunction "4_4") (pintype "input"))
    )
    (net (code "71") (name "unconnected-(U1-AIN1-Pad5)") (class "Default")
      (node (ref "U1") (pin "5") (pinfunction "AIN1_5") (pintype "bidirectional"))
    )
    (net (code "72") (name "unconnected-(U3-IO2-Pad24)") (class "Default")
      (node (ref "U3") (pin "24") (pinfunction "IO2_24") (pintype "bidirectional"))
    )
    (net (code "73") (name "unconnected-(U3-IO12-Pad14)") (class "Default")
      (node (ref "U3") (pin "14") (pinfunction "IO12_14") (pintype "bidirectional"))
    )
    (net (code "74") (name "unconnected-(U3-SCL{slash}CLK-Pad20)") (class "Default")
      (node (ref "U3") (pin "20") (pinfunction "SCL/CLK_20") (pintype "bidirectional"))
    )
    (net (code "75") (name "unconnected-(U3-SCS{slash}CMD-Pad19)") (class "Default")
      (node (ref "U3") (pin "19") (pinfunction "SCS/CMD_19") (pintype "bidirectional"))
    )
    (net (code "76") (name "unconnected-(U3-SDI{slash}SD1-Pad22)") (class "Default")
      (node (ref "U3") (pin "22") (pinfunction "SDI/SD1_22") (pintype "bidirectional"))
    )
    (net (code "77") (name "unconnected-(U3-SDO{slash}SD0-Pad21)") (class "Default")
      (node (ref "U3") (pin "21") (pinfunction "SDO/SD0_21") (pintype "bidirectional"))
    )
    (net (code "78") (name "unconnected-(U3-SENSOR_VN-Pad5)") (class "Default")
      (node (ref "U3") (pin "5") (pinfunction "SENSOR_VN_5") (pintype "input"))
    )
    (net (code "79") (name "unconnected-(U3-SENSOR_VP-Pad4)") (class "Default")
      (node (ref "U3") (pin "4") (pinfunction "SENSOR_VP_4") (pintype "input"))
    )
    (net (code "80") (name "unconnected-(U3-SHD{slash}SD2-Pad17)") (class "Default")
      (node (ref "U3") (pin "17") (pinfunction "SHD/SD2_17") (pintype "bidirectional"))
    )
    (net (code "81") (name "unconnected-(U3-SWP{slash}SD3-Pad18)") (class "Default")
      (node (ref "U3") (pin "18") (pinfunction "SWP/SD3_18") (pintype "bidirectional"))
    )
  )
)
